# OA.net
KiCad netlist of a schematic drawn in Altium Designer
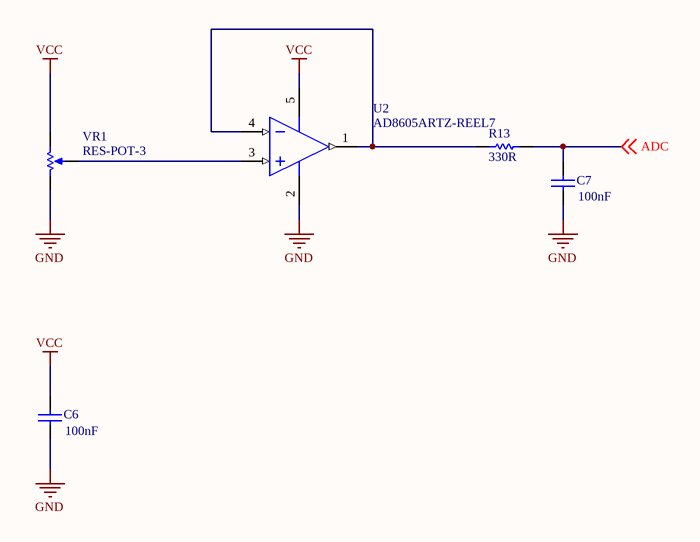
[diagram p0: OA.SchDoc]

(export (version "E")
  (design (tool "Eeschema 10.0.6"))
  (components
    (comp (ref "C6")
      (value "100nF")
      (footprint "CAPC0805(2012)75_M")
      (description "CAP 100nF 16V ±20% 0805 (2012 Metric) Thickness 0.75mm SMD")
      (fields (field (name "TOLERANCE") "Â±20%"))
      (libsource (lib "Altium Content Vault") (part "CMP-1036-04403-1"))
    )
    (comp (ref "C7")
      (value "100nF")
      (footprint "CAPC0805(2012)75_M")
      (description "CAP 100nF 16V ±20% 0805 (2012 Metric) Thickness 0.75mm SMD")
      (fields (field (name "TOLERANCE") "Â±20%"))
      (libsource (lib "Altium Content Vault") (part "CMP-1036-04403-1"))
    )
    (comp (ref "R13")
      (value "330R")
      (footprint "RESC0805(2012)_M")
      (description "330R 0.125W 5% 0805 (2012 Metric)  SMD")
      (fields (field (name "TOLERANCE") "5 %") (field (name "POWER") "0.125 W"))
      (libsource (lib "Altium Content Vault") (part "CMP-1013-00062-1"))
    )
    (comp (ref "U2")
      (value "AD8605ARTZ-REEL7")
      (footprint "ADI-RJ-5_M")
      (fields (field (name "MANUFACTURER") "Analog Devices") (field (name "GENERIC PART NUMBER") "AD8605"))
      (libsource (lib "Altium Content Vault") (part "CMP-0384-01494-2"))
    )
    (comp (ref "VR1")
      (value "RES-POT-3")
      (footprint "library pcb:RES-POT-3")
      (libsource (lib "library") (part "RES-POT-3"))
    )
  )
  (nets
    (net (code "1") (name "ADC") (class "Default")
      (node (ref "C7") (pin "2") (pinfunction "2_2") (pintype "passive"))
      (node (ref "R13") (pin "2") (pinfunction "2_2") (pintype "passive"))
    )
    (net (code "2") (name "GND") (class "Default")
      (node (ref "C6") (pin "1") (pinfunction "1_1") (pintype "passive"))
      (node (ref "C7") (pin "1") (pinfunction "1_1") (pintype "passive"))
      (node (ref "U2") (pin "2") (pinfunction "-V_2") (pintype "power_in"))
      (node (ref "VR1") (pin "3") (pinfunction "CW_3") (pintype "passive"))
    )
    (net (code "3") (name "Net-(U2-+IN)") (class "Default")
      (node (ref "U2") (pin "3") (pinfunction "+IN_3") (pintype "input"))
      (node (ref "VR1") (pin "2") (pinfunction "S_2") (pintype "passive"))
    )
    (net (code "4") (name "Net-(U2--IN)") (class "Default")
      (node (ref "R13") (pin "1") (pinfunction "1_1") (pintype "passive"))
      (node (ref "U2") (pin "1") (pinfunction "OUT_1") (pintype "output"))
      (node (ref "U2") (pin "4") (pinfunction "-IN_4") (pintype "input"))
    )
    (net (code "5") (name "VCC") (class "Default")
      (node (ref "C6") (pin "2") (pinfunction "2_2") (pintype "passive"))
      (node (ref "U2") (pin "5") (pinfunction "+V_5") (pintype "power_in"))
      (node (ref "VR1") (pin "1") (pinfunction "CCW_1") (pintype "passive"))
    )
  )
)
